# MCPv5_eingabe.net
KiCad netlist of a schematic drawn in EAGLE
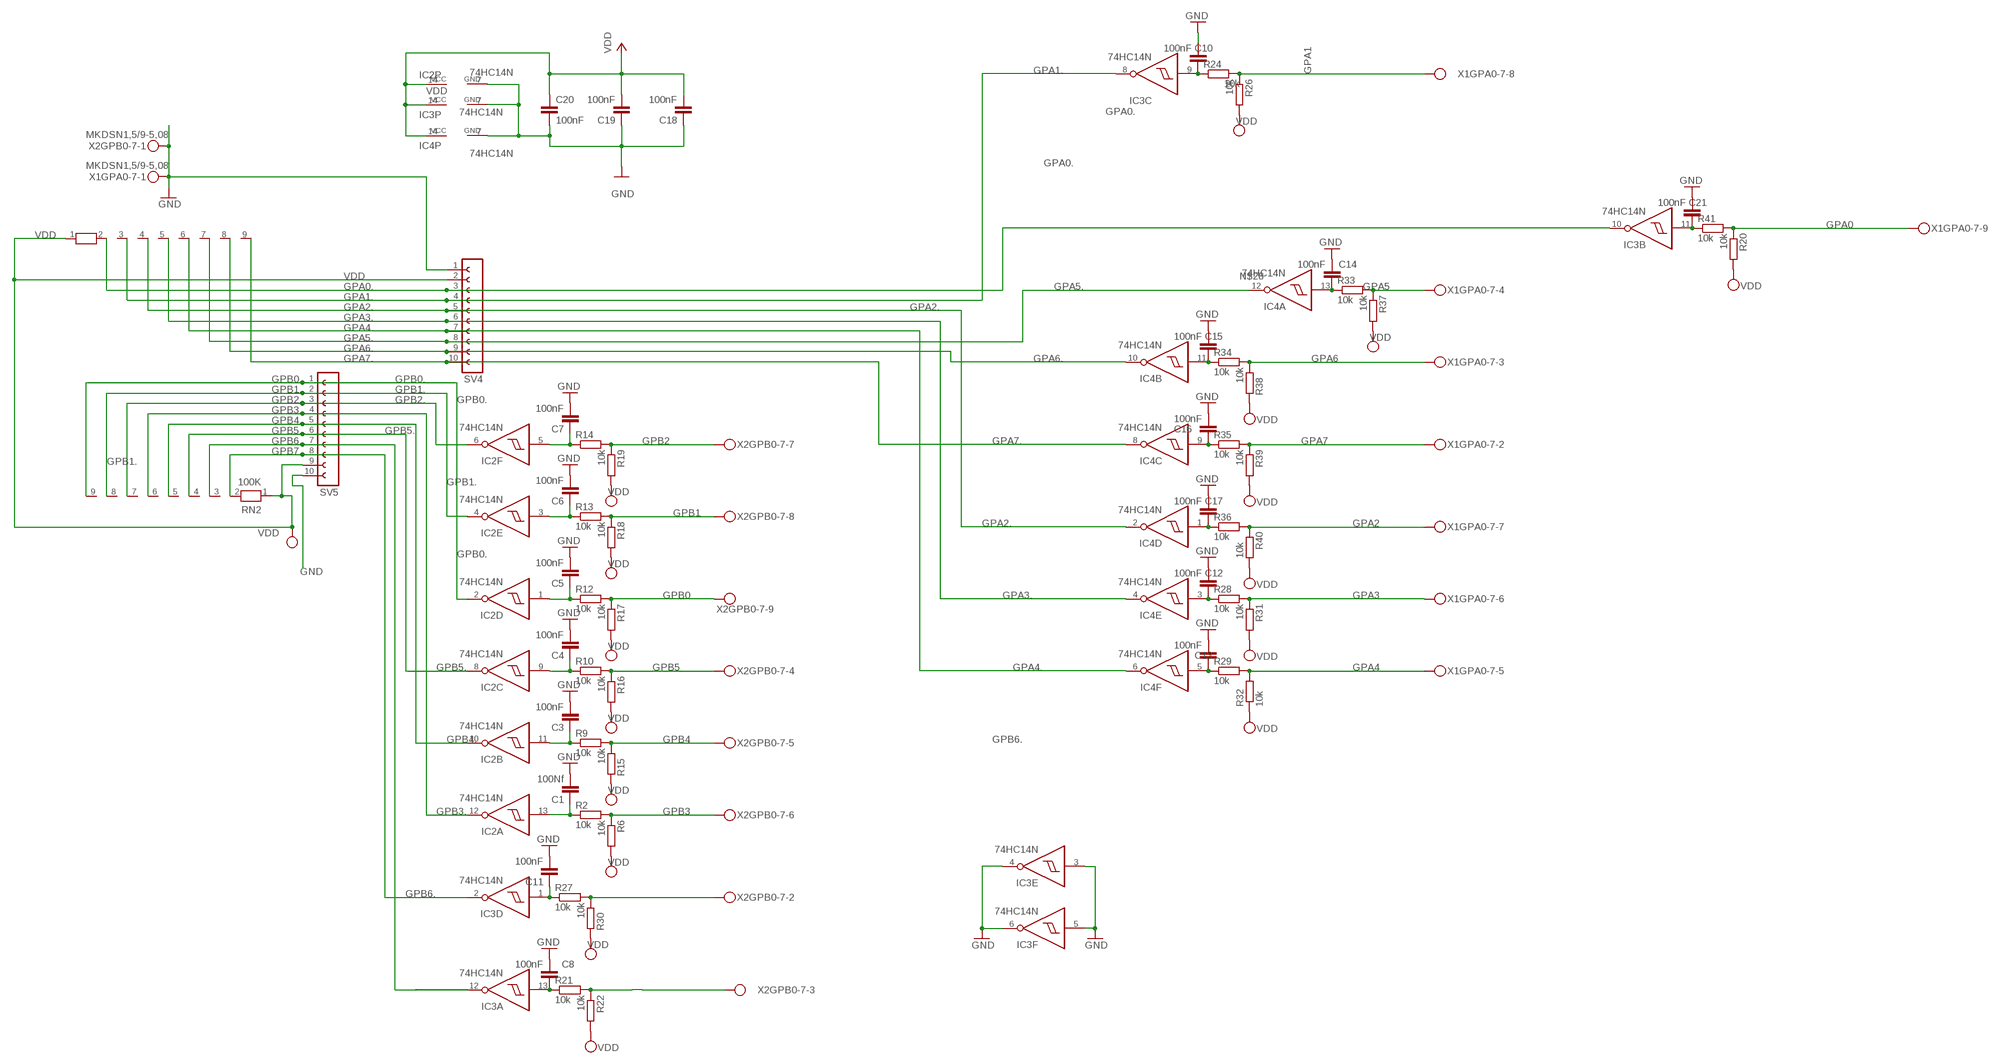
[diagram p0: schematic, sheet 1]

(export (version "E")
  (design (tool "Eeschema 10.0.6"))
  (components
    (comp (ref "C1")
      (value "100Nf")
      (footprint "eagle-import:C025-024X044")
      (libsource (lib "eagle-import") (part "C-EU025-024X044"))
    )
    (comp (ref "C3")
      (value "100nF")
      (footprint "eagle-import:C025-024X044")
      (libsource (lib "eagle-import") (part "C-EU025-024X044"))
    )
    (comp (ref "C4")
      (value "100nF")
      (footprint "eagle-import:C025-024X044")
      (libsource (lib "eagle-import") (part "C-EU025-024X044"))
    )
    (comp (ref "C5")
      (value "100nF")
      (footprint "eagle-import:C025-024X044")
      (libsource (lib "eagle-import") (part "C-EU025-024X044"))
    )
    (comp (ref "C6")
      (value "100nF")
      (footprint "eagle-import:C025-024X044")
      (libsource (lib "eagle-import") (part "C-EU025-024X044"))
    )
    (comp (ref "C7")
      (value "100nF")
      (footprint "eagle-import:C025-024X044")
      (libsource (lib "eagle-import") (part "C-EU025-024X044"))
    )
    (comp (ref "C8")
      (value "100nF")
      (footprint "eagle-import:C025-024X044")
      (libsource (lib "eagle-import") (part "C-EU025-024X044"))
    )
    (comp (ref "C10")
      (value "100nF")
      (footprint "eagle-import:C025-024X044")
      (libsource (lib "eagle-import") (part "C-EU025-024X044"))
    )
    (comp (ref "C11")
      (value "100nF")
      (footprint "eagle-import:C025-024X044")
      (libsource (lib "eagle-import") (part "C-EU025-024X044"))
    )
    (comp (ref "C12")
      (value "100nF")
      (footprint "eagle-import:C025-024X044")
      (libsource (lib "eagle-import") (part "C-EU025-024X044"))
    )
    (comp (ref "C13")
      (value "100nF")
      (footprint "eagle-import:C025-024X044")
      (libsource (lib "eagle-import") (part "C-EU025-024X044"))
    )
    (comp (ref "C14")
      (value "100nF")
      (footprint "eagle-import:C025-024X044")
      (libsource (lib "eagle-import") (part "C-EU025-024X044"))
    )
    (comp (ref "C15")
      (value "100nF")
      (footprint "eagle-import:C025-024X044")
      (libsource (lib "eagle-import") (part "C-EU025-024X044"))
    )
    (comp (ref "C16")
      (value "100nF")
      (footprint "eagle-import:C025-024X044")
      (libsource (lib "eagle-import") (part "C-EU025-024X044"))
    )
    (comp (ref "C17")
      (value "100nF")
      (footprint "eagle-import:C025-024X044")
      (libsource (lib "eagle-import") (part "C-EU025-024X044"))
    )
    (comp (ref "C18")
      (value "100nF")
      (footprint "eagle-import:C025-024X044")
      (libsource (lib "eagle-import") (part "C-EU025-024X044"))
    )
    (comp (ref "C19")
      (value "100nF")
      (footprint "eagle-import:C025-024X044")
      (libsource (lib "eagle-import") (part "C-EU025-024X044"))
    )
    (comp (ref "C20")
      (value "100nF")
      (footprint "eagle-import:C025-024X044")
      (libsource (lib "eagle-import") (part "C-EU025-024X044"))
    )
    (comp (ref "C21")
      (value "100nF")
      (footprint "eagle-import:C025-024X044")
      (libsource (lib "eagle-import") (part "C-EU025-024X044"))
    )
    (comp (ref "IC2")
      (value "74HC14N")
      (footprint "eagle-import:DIL14")
      (libsource (lib "eagle-import") (part "7414NHC"))
    )
    (comp (ref "IC3")
      (value "74HC14N")
      (footprint "eagle-import:DIL14")
      (libsource (lib "eagle-import") (part "7414NHC"))
    )
    (comp (ref "IC4")
      (value "74HC14N")
      (footprint "eagle-import:DIL14")
      (libsource (lib "eagle-import") (part "7414NHC"))
    )
    (comp (ref "R2")
      (value "10k")
      (footprint "eagle-import:0204_7")
      (libsource (lib "eagle-import") (part "R-EU_0204/7"))
    )
    (comp (ref "R6")
      (value "10k")
      (footprint "eagle-import:0204_7")
      (libsource (lib "eagle-import") (part "R-EU_0204/7"))
    )
    (comp (ref "R9")
      (value "10k")
      (footprint "eagle-import:0204_7")
      (libsource (lib "eagle-import") (part "R-EU_0204/7"))
    )
    (comp (ref "R10")
      (value "10k")
      (footprint "eagle-import:0204_7")
      (libsource (lib "eagle-import") (part "R-EU_0204/7"))
    )
    (comp (ref "R12")
      (value "10k")
      (footprint "eagle-import:0204_7")
      (libsource (lib "eagle-import") (part "R-EU_0204/7"))
    )
    (comp (ref "R13")
      (value "10k")
      (footprint "eagle-import:0204_7")
      (libsource (lib "eagle-import") (part "R-EU_0204/7"))
    )
    (comp (ref "R14")
      (value "10k")
      (footprint "eagle-import:0204_7")
      (libsource (lib "eagle-import") (part "R-EU_0204/7"))
    )
    (comp (ref "R15")
      (value "10k")
      (footprint "eagle-import:0204_7")
      (libsource (lib "eagle-import") (part "R-EU_0204/7"))
    )
    (comp (ref "R16")
      (value "10k")
      (footprint "eagle-import:0204_7")
      (libsource (lib "eagle-import") (part "R-EU_0204/7"))
    )
    (comp (ref "R17")
      (value "10k")
      (footprint "eagle-import:0204_7")
      (libsource (lib "eagle-import") (part "R-EU_0204/7"))
    )
    (comp (ref "R18")
      (value "10k")
      (footprint "eagle-import:0204_7")
      (libsource (lib "eagle-import") (part "R-EU_0204/7"))
    )
    (comp (ref "R19")
      (value "10k")
      (footprint "eagle-import:0204_7")
      (libsource (lib "eagle-import") (part "R-EU_0204/7"))
    )
    (comp (ref "R20")
      (value "10k")
      (footprint "eagle-import:0204_7")
      (libsource (lib "eagle-import") (part "R-EU_0204/7"))
    )
    (comp (ref "R21")
      (value "10k")
      (footprint "eagle-import:0204_7")
      (libsource (lib "eagle-import") (part "R-EU_0204/7"))
    )
    (comp (ref "R22")
      (value "10k")
      (footprint "eagle-import:0204_7")
      (libsource (lib "eagle-import") (part "R-EU_0204/7"))
    )
    (comp (ref "R24")
      (value "10k")
      (footprint "eagle-import:0204_7")
      (libsource (lib "eagle-import") (part "R-EU_0204/7"))
    )
    (comp (ref "R26")
      (value "10k")
      (footprint "eagle-import:0204_7")
      (libsource (lib "eagle-import") (part "R-EU_0204/7"))
    )
    (comp (ref "R27")
      (value "10k")
      (footprint "eagle-import:0204_7")
      (libsource (lib "eagle-import") (part "R-EU_0204/7"))
    )
    (comp (ref "R28")
      (value "10k")
      (footprint "eagle-import:0204_7")
      (libsource (lib "eagle-import") (part "R-EU_0204/7"))
    )
    (comp (ref "R29")
      (value "10k")
      (footprint "eagle-import:0204_7")
      (libsource (lib "eagle-import") (part "R-EU_0204/7"))
    )
    (comp (ref "R30")
      (value "10k")
      (footprint "eagle-import:0204_7")
      (libsource (lib "eagle-import") (part "R-EU_0204/7"))
    )
    (comp (ref "R31")
      (value "10k")
      (footprint "eagle-import:0204_7")
      (libsource (lib "eagle-import") (part "R-EU_0204/7"))
    )
    (comp (ref "R32")
      (value "10k")
      (footprint "eagle-import:0204_7")
      (libsource (lib "eagle-import") (part "R-EU_0204/7"))
    )
    (comp (ref "R33")
      (value "10k")
      (footprint "eagle-import:0204_7")
      (libsource (lib "eagle-import") (part "R-EU_0204/7"))
    )
    (comp (ref "R34")
      (value "10k")
      (footprint "eagle-import:0204_7")
      (libsource (lib "eagle-import") (part "R-EU_0204/7"))
    )
    (comp (ref "R35")
      (value "10k")
      (footprint "eagle-import:0204_7")
      (libsource (lib "eagle-import") (part "R-EU_0204/7"))
    )
    (comp (ref "R36")
      (value "10k")
      (footprint "eagle-import:0204_7")
      (libsource (lib "eagle-import") (part "R-EU_0204/7"))
    )
    (comp (ref "R37")
      (value "10k")
      (footprint "eagle-import:0204_7")
      (libsource (lib "eagle-import") (part "R-EU_0204/7"))
    )
    (comp (ref "R38")
      (value "10k")
      (footprint "eagle-import:0204_7")
      (libsource (lib "eagle-import") (part "R-EU_0204/7"))
    )
    (comp (ref "R39")
      (value "10k")
      (footprint "eagle-import:0204_7")
      (libsource (lib "eagle-import") (part "R-EU_0204/7"))
    )
    (comp (ref "R40")
      (value "10k")
      (footprint "eagle-import:0204_7")
      (libsource (lib "eagle-import") (part "R-EU_0204/7"))
    )
    (comp (ref "R41")
      (value "10k")
      (footprint "eagle-import:0204_7")
      (libsource (lib "eagle-import") (part "R-EU_0204/7"))
    )
    (comp (ref "RN1")
      (value "100K")
      (footprint "eagle-import:RN-9")
      (fields (field (name "SPICEPREFIX") "X"))
      (libsource (lib "eagle-import") (part "RN08"))
    )
    (comp (ref "RN2")
      (value "100K")
      (footprint "eagle-import:RN-9")
      (libsource (lib "eagle-import") (part "RN08"))
    )
    (comp (ref "SV4")
      (value "FE10-1")
      (footprint "eagle-import:FE10")
      (libsource (lib "eagle-import") (part "FE10-1"))
    )
    (comp (ref "SV5")
      (value "FE10-1")
      (footprint "eagle-import:FE10")
      (libsource (lib "eagle-import") (part "FE10-1"))
    )
    (comp (ref "X1GPA0-7")
      (value "MKDSN1,5/9-5,08")
      (footprint "eagle-import:MKDSN1,5_9-5,08")
      (libsource (lib "eagle-import") (part "MKDSN1,5/9-5,08"))
    )
    (comp (ref "X2GPB0-7")
      (value "MKDSN1,5/9-5,08")
      (footprint "eagle-import:MKDSN1,5_9-5,08")
      (libsource (lib "eagle-import") (part "MKDSN1,5/9-5,08"))
    )
  )
  (nets
    (net (code "1") (name "/GPA0") (class "Default")
      (node (ref "R20") (pin "1") (pinfunction "1_1") (pintype "passive"))
      (node (ref "R41") (pin "2") (pinfunction "2_2") (pintype "passive"))
      (node (ref "X1GPA0-7") (pin "9") (pinfunction "KL_9") (pintype "passive"))
    )
    (net (code "2") (name "/GPA0.") (class "Default")
      (node (ref "IC3") (pin "10") (pinfunction "O_10") (pintype "output"))
      (node (ref "RN1") (pin "2") (pinfunction "2_2") (pintype "passive"))
      (node (ref "SV4") (pin "3") (pinfunction "3_3") (pintype "passive"))
    )
    (net (code "3") (name "/GPA1") (class "Default")
      (node (ref "R24") (pin "2") (pinfunction "2_2") (pintype "passive"))
      (node (ref "R26") (pin "1") (pinfunction "1_1") (pintype "passive"))
      (node (ref "X1GPA0-7") (pin "8") (pinfunction "KL_8") (pintype "passive"))
    )
    (net (code "4") (name "/GPA1.") (class "Default")
      (node (ref "IC3") (pin "8") (pinfunction "O_8") (pintype "output"))
      (node (ref "RN1") (pin "3") (pinfunction "3_3") (pintype "passive"))
      (node (ref "SV4") (pin "4") (pinfunction "4_4") (pintype "passive"))
    )
    (net (code "5") (name "/GPA2") (class "Default")
      (node (ref "R36") (pin "2") (pinfunction "2_2") (pintype "passive"))
      (node (ref "R40") (pin "1") (pinfunction "1_1") (pintype "passive"))
      (node (ref "X1GPA0-7") (pin "7") (pinfunction "KL_7") (pintype "passive"))
    )
    (net (code "6") (name "/GPA2.") (class "Default")
      (node (ref "IC4") (pin "2") (pinfunction "O_2") (pintype "output"))
      (node (ref "RN1") (pin "4") (pinfunction "4_4") (pintype "passive"))
      (node (ref "SV4") (pin "5") (pinfunction "5_5") (pintype "passive"))
    )
    (net (code "7") (name "/GPA3") (class "Default")
      (node (ref "R28") (pin "2") (pinfunction "2_2") (pintype "passive"))
      (node (ref "R31") (pin "1") (pinfunction "1_1") (pintype "passive"))
      (node (ref "X1GPA0-7") (pin "6") (pinfunction "KL_6") (pintype "passive"))
    )
    (net (code "8") (name "/GPA3.") (class "Default")
      (node (ref "IC4") (pin "4") (pinfunction "O_4") (pintype "output"))
      (node (ref "RN1") (pin "5") (pinfunction "5_5") (pintype "passive"))
      (node (ref "SV4") (pin "6") (pinfunction "6_6") (pintype "passive"))
    )
    (net (code "9") (name "/GPA4") (class "Default")
      (node (ref "R29") (pin "2") (pinfunction "2_2") (pintype "passive"))
      (node (ref "R32") (pin "2") (pinfunction "2_2") (pintype "passive"))
      (node (ref "X1GPA0-7") (pin "5") (pinfunction "KL_5") (pintype "passive"))
    )
    (net (code "10") (name "/GPA4.") (class "Default")
      (node (ref "IC4") (pin "6") (pinfunction "O_6") (pintype "output"))
      (node (ref "RN1") (pin "6") (pinfunction "6_6") (pintype "passive"))
      (node (ref "SV4") (pin "7") (pinfunction "7_7") (pintype "passive"))
    )
    (net (code "11") (name "/GPA5") (class "Default")
      (node (ref "R33") (pin "2") (pinfunction "2_2") (pintype "passive"))
      (node (ref "R37") (pin "1") (pinfunction "1_1") (pintype "passive"))
      (node (ref "X1GPA0-7") (pin "4") (pinfunction "KL_4") (pintype "passive"))
    )
    (net (code "12") (name "/GPA5.") (class "Default")
      (node (ref "IC4") (pin "12") (pinfunction "O_12") (pintype "output"))
      (node (ref "RN1") (pin "7") (pinfunction "7_7") (pintype "passive"))
      (node (ref "SV4") (pin "8") (pinfunction "8_8") (pintype "passive"))
    )
    (net (code "13") (name "/GPA6") (class "Default")
      (node (ref "R34") (pin "2") (pinfunction "2_2") (pintype "passive"))
      (node (ref "R38") (pin "1") (pinfunction "1_1") (pintype "passive"))
      (node (ref "X1GPA0-7") (pin "3") (pinfunction "KL_3") (pintype "passive"))
    )
    (net (code "14") (name "/GPA6.") (class "Default")
      (node (ref "IC4") (pin "10") (pinfunction "O_10") (pintype "output"))
      (node (ref "RN1") (pin "8") (pinfunction "8_8") (pintype "passive"))
      (node (ref "SV4") (pin "9") (pinfunction "9_9") (pintype "passive"))
    )
    (net (code "15") (name "/GPA7") (class "Default")
      (node (ref "R35") (pin "2") (pinfunction "2_2") (pintype "passive"))
      (node (ref "R39") (pin "1") (pinfunction "1_1") (pintype "passive"))
      (node (ref "X1GPA0-7") (pin "2") (pinfunction "KL_2") (pintype "passive"))
    )
    (net (code "16") (name "/GPA7.") (class "Default")
      (node (ref "IC4") (pin "8") (pinfunction "O_8") (pintype "output"))
      (node (ref "RN1") (pin "9") (pinfunction "9_9") (pintype "passive"))
      (node (ref "SV4") (pin "10") (pinfunction "10_10") (pintype "passive"))
    )
    (net (code "17") (name "/GPB0") (class "Default")
      (node (ref "R12") (pin "2") (pinfunction "2_2") (pintype "passive"))
      (node (ref "R17") (pin "1") (pinfunction "1_1") (pintype "passive"))
      (node (ref "X2GPB0-7") (pin "9") (pinfunction "KL_9") (pintype "passive"))
    )
    (net (code "18") (name "/GPB0.") (class "Default")
      (node (ref "IC2") (pin "2") (pinfunction "O_2") (pintype "output"))
      (node (ref "RN2") (pin "9") (pinfunction "9_9") (pintype "passive"))
      (node (ref "SV5") (pin "1") (pinfunction "1_1") (pintype "passive"))
    )
    (net (code "19") (name "/GPB1") (class "Default")
      (node (ref "R13") (pin "2") (pinfunction "2_2") (pintype "passive"))
      (node (ref "R18") (pin "1") (pinfunction "1_1") (pintype "passive"))
      (node (ref "X2GPB0-7") (pin "8") (pinfunction "KL_8") (pintype "passive"))
    )
    (net (code "20") (name "/GPB1.") (class "Default")
      (node (ref "IC2") (pin "4") (pinfunction "O_4") (pintype "output"))
      (node (ref "RN2") (pin "8") (pinfunction "8_8") (pintype "passive"))
      (node (ref "SV5") (pin "2") (pinfunction "2_2") (pintype "passive"))
    )
    (net (code "21") (name "/GPB2") (class "Default")
      (node (ref "R14") (pin "2") (pinfunction "2_2") (pintype "passive"))
      (node (ref "R19") (pin "1") (pinfunction "1_1") (pintype "passive"))
      (node (ref "X2GPB0-7") (pin "7") (pinfunction "KL_7") (pintype "passive"))
    )
    (net (code "22") (name "/GPB2.") (class "Default")
      (node (ref "IC2") (pin "6") (pinfunction "O_6") (pintype "output"))
      (node (ref "RN2") (pin "7") (pinfunction "7_7") (pintype "passive"))
      (node (ref "SV5") (pin "3") (pinfunction "3_3") (pintype "passive"))
    )
    (net (code "23") (name "/GPB3") (class "Default")
      (node (ref "R2") (pin "2") (pinfunction "2_2") (pintype "passive"))
      (node (ref "R6") (pin "1") (pinfunction "1_1") (pintype "passive"))
      (node (ref "X2GPB0-7") (pin "6") (pinfunction "KL_6") (pintype "passive"))
    )
    (net (code "24") (name "/GPB3.") (class "Default")
      (node (ref "IC2") (pin "12") (pinfunction "O_12") (pintype "output"))
      (node (ref "RN2") (pin "6") (pinfunction "6_6") (pintype "passive"))
      (node (ref "SV5") (pin "4") (pinfunction "4_4") (pintype "passive"))
    )
    (net (code "25") (name "/GPB4") (class "Default")
      (node (ref "R15") (pin "1") (pinfunction "1_1") (pintype "passive"))
      (node (ref "R9") (pin "2") (pinfunction "2_2") (pintype "passive"))
      (node (ref "X2GPB0-7") (pin "5") (pinfunction "KL_5") (pintype "passive"))
    )
    (net (code "26") (name "/GPB4.") (class "Default")
      (node (ref "IC2") (pin "10") (pinfunction "O_10") (pintype "output"))
      (node (ref "RN2") (pin "5") (pinfunction "5_5") (pintype "passive"))
      (node (ref "SV5") (pin "5") (pinfunction "5_5") (pintype "passive"))
    )
    (net (code "27") (name "/GPB5") (class "Default")
      (node (ref "R10") (pin "2") (pinfunction "2_2") (pintype "passive"))
      (node (ref "R16") (pin "1") (pinfunction "1_1") (pintype "passive"))
      (node (ref "X2GPB0-7") (pin "4") (pinfunction "KL_4") (pintype "passive"))
    )
    (net (code "28") (name "/GPB5.") (class "Default")
      (node (ref "IC2") (pin "8") (pinfunction "O_8") (pintype "output"))
      (node (ref "RN2") (pin "4") (pinfunction "4_4") (pintype "passive"))
      (node (ref "SV5") (pin "6") (pinfunction "6_6") (pintype "passive"))
    )
    (net (code "29") (name "/GPB6.") (class "Default")
      (node (ref "IC3") (pin "12") (pinfunction "O_12") (pintype "output"))
      (node (ref "RN2") (pin "3") (pinfunction "3_3") (pintype "passive"))
      (node (ref "SV5") (pin "7") (pinfunction "7_7") (pintype "passive"))
    )
    (net (code "30") (name "/GPB7.") (class "Default")
      (node (ref "IC3") (pin "2") (pinfunction "O_2") (pintype "output"))
      (node (ref "RN2") (pin "2") (pinfunction "2_2") (pintype "passive"))
      (node (ref "SV5") (pin "8") (pinfunction "8_8") (pintype "passive"))
    )
    (net (code "32") (name "GND") (class "Default")
      (node (ref "C1") (pin "2") (pinfunction "2_2") (pintype "passive"))
      (node (ref "C10") (pin "2") (pinfunction "2_2") (pintype "passive"))
      (node (ref "C11") (pin "2") (pinfunction "2_2") (pintype "passive"))
      (node (ref "C12") (pin "2") (pinfunction "2_2") (pintype "passive"))
      (node (ref "C13") (pin "2") (pinfunction "2_2") (pintype "passive"))
      (node (ref "C14") (pin "2") (pinfunction "2_2") (pintype "passive"))
      (node (ref "C15") (pin "2") (pinfunction "2_2") (pintype "passive"))
      (node (ref "C16") (pin "2") (pinfunction "2_2") (pintype "passive"))
      (node (ref "C17") (pin "2") (pinfunction "2_2") (pintype "passive"))
      (node (ref "C18") (pin "1") (pinfunction "1_1") (pintype "passive"))
      (node (ref "C19") (pin "1") (pinfunction "1_1") (pintype "passive"))
      (node (ref "C20") (pin "2") (pinfunction "2_2") (pintype "passive"))
      (node (ref "C21") (pin "2") (pinfunction "2_2") (pintype "passive"))
      (node (ref "C3") (pin "2") (pinfunction "2_2") (pintype "passive"))
      (node (ref "C4") (pin "2") (pinfunction "2_2") (pintype "passive"))
      (node (ref "C5") (pin "2") (pinfunction "2_2") (pintype "passive"))
      (node (ref "C6") (pin "2") (pinfunction "2_2") (pintype "passive"))
      (node (ref "C7") (pin "2") (pinfunction "2_2") (pintype "passive"))
      (node (ref "C8") (pin "2") (pinfunction "2_2") (pintype "passive"))
      (node (ref "IC2") (pin "7") (pinfunction "GND_7") (pintype "power_in"))
      (node (ref "IC3") (pin "3") (pinfunction "I_3") (pintype "input"))
      (node (ref "IC3") (pin "4") (pinfunction "O_4") (pintype "output"))
      (node (ref "IC3") (pin "5") (pinfunction "I_5") (pintype "input"))
      (node (ref "IC3") (pin "6") (pinfunction "O_6") (pintype "output"))
      (node (ref "IC3") (pin "7") (pinfunction "GND_7") (pintype "power_in"))
      (node (ref "IC4") (pin "7") (pinfunction "GND_7") (pintype "power_in"))
      (node (ref "SV4") (pin "1") (pinfunction "1_1") (pintype "passive"))
      (node (ref "SV5") (pin "10") (pinfunction "10_10") (pintype "passive"))
      (node (ref "X1GPA0-7") (pin "1") (pinfunction "KL_1") (pintype "passive"))
      (node (ref "X2GPB0-7") (pin "1") (pinfunction "KL_1") (pintype "passive"))
    )
    (net (code "33") (name "Net-(IC2A-I)") (class "Default")
      (node (ref "C1") (pin "1") (pinfunction "1_1") (pintype "passive"))
      (node (ref "IC2") (pin "13") (pinfunction "I_13") (pintype "input"))
      (node (ref "R2") (pin "1") (pinfunction "1_1") (pintype "passive"))
    )
    (net (code "34") (name "Net-(IC2B-I)") (class "Default")
      (node (ref "C3") (pin "1") (pinfunction "1_1") (pintype "passive"))
      (node (ref "IC2") (pin "11") (pinfunction "I_11") (pintype "input"))
      (node (ref "R9") (pin "1") (pinfunction "1_1") (pintype "passive"))
    )
    (net (code "35") (name "Net-(IC2C-I)") (class "Default")
      (node (ref "C4") (pin "1") (pinfunction "1_1") (pintype "passive"))
      (node (ref "IC2") (pin "9") (pinfunction "I_9") (pintype "input"))
      (node (ref "R10") (pin "1") (pinfunction "1_1") (pintype "passive"))
    )
    (net (code "36") (name "Net-(IC2D-I)") (class "Default")
      (node (ref "C5") (pin "1") (pinfunction "1_1") (pintype "passive"))
      (node (ref "IC2") (pin "1") (pinfunction "I_1") (pintype "input"))
      (node (ref "R12") (pin "1") (pinfunction "1_1") (pintype "passive"))
    )
    (net (code "37") (name "Net-(IC2E-I)") (class "Default")
      (node (ref "C6") (pin "1") (pinfunction "1_1") (pintype "passive"))
      (node (ref "IC2") (pin "3") (pinfunction "I_3") (pintype "input"))
      (node (ref "R13") (pin "1") (pinfunction "1_1") (pintype "passive"))
    )
    (net (code "38") (name "Net-(IC2F-I)") (class "Default")
      (node (ref "C7") (pin "1") (pinfunction "1_1") (pintype "passive"))
      (node (ref "IC2") (pin "5") (pinfunction "I_5") (pintype "input"))
      (node (ref "R14") (pin "1") (pinfunction "1_1") (pintype "passive"))
    )
    (net (code "39") (name "Net-(IC3A-I)") (class "Default")
      (node (ref "C8") (pin "1") (pinfunction "1_1") (pintype "passive"))
      (node (ref "IC3") (pin "13") (pinfunction "I_13") (pintype "input"))
      (node (ref "R21") (pin "1") (pinfunction "1_1") (pintype "passive"))
    )
    (net (code "40") (name "Net-(IC3B-I)") (class "Default")
      (node (ref "C21") (pin "1") (pinfunction "1_1") (pintype "passive"))
      (node (ref "IC3") (pin "11") (pinfunction "I_11") (pintype "input"))
      (node (ref "R41") (pin "1") (pinfunction "1_1") (pintype "passive"))
    )
    (net (code "41") (name "Net-(IC3C-I)") (class "Default")
      (node (ref "C10") (pin "1") (pinfunction "1_1") (pintype "passive"))
      (node (ref "IC3") (pin "9") (pinfunction "I_9") (pintype "input"))
      (node (ref "R24") (pin "1") (pinfunction "1_1") (pintype "passive"))
    )
    (net (code "42") (name "Net-(IC3D-I)") (class "Default")
      (node (ref "C11") (pin "1") (pinfunction "1_1") (pintype "passive"))
      (node (ref "IC3") (pin "1") (pinfunction "I_1") (pintype "input"))
      (node (ref "R27") (pin "1") (pinfunction "1_1") (pintype "passive"))
    )
    (net (code "43") (name "Net-(IC4A-I)") (class "Default")
      (node (ref "C14") (pin "1") (pinfunction "1_1") (pintype "passive"))
      (node (ref "IC4") (pin "13") (pinfunction "I_13") (pintype "input"))
      (node (ref "R33") (pin "1") (pinfunction "1_1") (pintype "passive"))
    )
    (net (code "44") (name "Net-(IC4B-I)") (class "Default")
      (node (ref "C15") (pin "1") (pinfunction "1_1") (pintype "passive"))
      (node (ref "IC4") (pin "11") (pinfunction "I_11") (pintype "input"))
      (node (ref "R34") (pin "1") (pinfunction "1_1") (pintype "passive"))
    )
    (net (code "45") (name "Net-(IC4C-I)") (class "Default")
      (node (ref "C16") (pin "1") (pinfunction "1_1") (pintype "passive"))
      (node (ref "IC4") (pin "9") (pinfunction "I_9") (pintype "input"))
      (node (ref "R35") (pin "1") (pinfunction "1_1") (pintype "passive"))
    )
    (net (code "46") (name "Net-(IC4D-I)") (class "Default")
      (node (ref "C17") (pin "1") (pinfunction "1_1") (pintype "passive"))
      (node (ref "IC4") (pin "1") (pinfunction "I_1") (pintype "input"))
      (node (ref "R36") (pin "1") (pinfunction "1_1") (pintype "passive"))
    )
    (net (code "47") (name "Net-(IC4E-I)") (class "Default")
      (node (ref "C12") (pin "1") (pinfunction "1_1") (pintype "passive"))
      (node (ref "IC4") (pin "3") (pinfunction "I_3") (pintype "input"))
      (node (ref "R28") (pin "1") (pinfunction "1_1") (pintype "passive"))
    )
    (net (code "48") (name "Net-(IC4F-I)") (class "Default")
      (node (ref "C13") (pin "1") (pinfunction "1_1") (pintype "passive"))
      (node (ref "IC4") (pin "5") (pinfunction "I_5") (pintype "input"))
      (node (ref "R29") (pin "1") (pinfunction "1_1") (pintype "passive"))
    )
    (net (code "49") (name "Net-(X2GPB0-7B-KL)") (class "Default")
      (node (ref "R27") (pin "2") (pinfunction "2_2") (pintype "passive"))
      (node (ref "R30") (pin "1") (pinfunction "1_1") (pintype "passive"))
      (node (ref "X2GPB0-7") (pin "2") (pinfunction "KL_2") (pintype "passive"))
    )
    (net (code "50") (name "Net-(X2GPB0-7C-KL)") (class "Default")
      (node (ref "R21") (pin "2") (pinfunction "2_2") (pintype "passive"))
      (node (ref "R22") (pin "1") (pinfunction "1_1") (pintype "passive"))
      (node (ref "X2GPB0-7") (pin "3") (pinfunction "KL_3") (pintype "passive"))
    )
    (net (code "51") (name "VDD") (class "Default")
      (node (ref "C18") (pin "2") (pinfunction "2_2") (pintype "passive"))
      (node (ref "C19") (pin "2") (pinfunction "2_2") (pintype "passive"))
      (node (ref "C20") (pin "1") (pinfunction "1_1") (pintype "passive"))
      (node (ref "IC2") (pin "14") (pinfunction "VCC_14") (pintype "power_in"))
      (node (ref "IC3") (pin "14") (pinfunction "VCC_14") (pintype "power_in"))
      (node (ref "IC4") (pin "14") (pinfunction "VCC_14") (pintype "power_in"))
      (node (ref "R15") (pin "2") (pinfunction "2_2") (pintype "passive"))
      (node (ref "R16") (pin "2") (pinfunction "2_2") (pintype "passive"))
      (node (ref "R17") (pin "2") (pinfunction "2_2") (pintype "passive"))
      (node (ref "R18") (pin "2") (pinfunction "2_2") (pintype "passive"))
      (node (ref "R19") (pin "2") (pinfunction "2_2") (pintype "passive"))
      (node (ref "R20") (pin "2") (pinfunction "2_2") (pintype "passive"))
      (node (ref "R22") (pin "2") (pinfunction "2_2") (pintype "passive"))
      (node (ref "R26") (pin "2") (pinfunction "2_2") (pintype "passive"))
      (node (ref "R30") (pin "2") (pinfunction "2_2") (pintype "passive"))
      (node (ref "R31") (pin "2") (pinfunction "2_2") (pintype "passive"))
      (node (ref "R32") (pin "1") (pinfunction "1_1") (pintype "passive"))
      (node (ref "R37") (pin "2") (pinfunction "2_2") (pintype "passive"))
      (node (ref "R38") (pin "2") (pinfunction "2_2") (pintype "passive"))
      (node (ref "R39") (pin "2") (pinfunction "2_2") (pintype "passive"))
      (node (ref "R40") (pin "2") (pinfunction "2_2") (pintype "passive"))
      (node (ref "R6") (pin "2") (pinfunction "2_2") (pintype "passive"))
      (node (ref "RN1") (pin "1") (pinfunction "1_1") (pintype "passive"))
      (node (ref "RN2") (pin "1") (pinfunction "1_1") (pintype "passive"))
      (node (ref "SV4") (pin "2") (pinfunction "2_2") (pintype "passive"))
      (node (ref "SV5") (pin "9") (pinfunction "9_9") (pintype "passive"))
    )
  )
)
